# MyPulseSensor.net
KiCad netlist of a schematic drawn in EAGLE
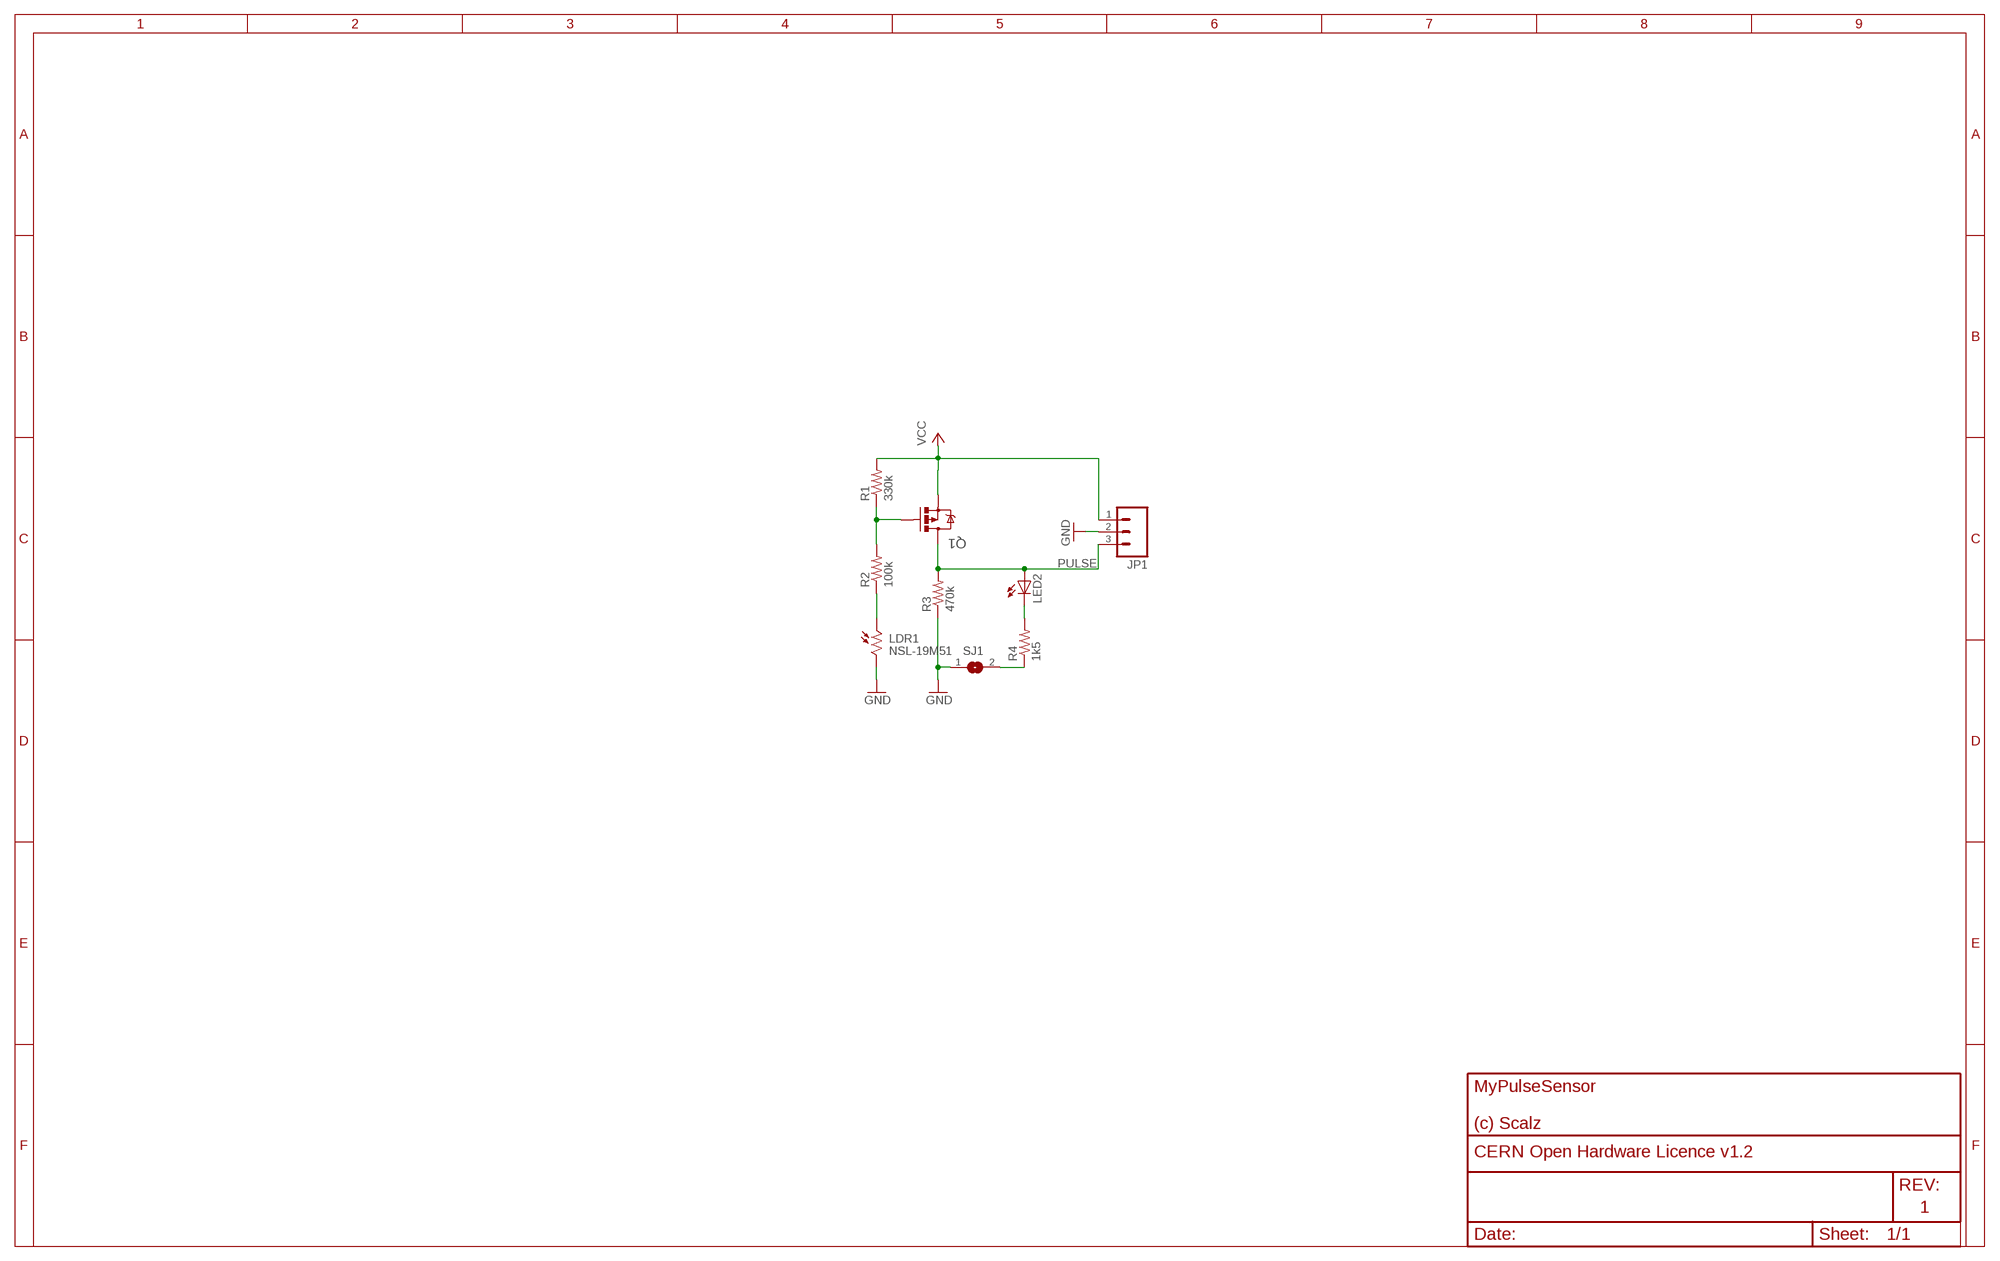
[diagram p0: schematic, sheet 1]

(export (version "E")
  (design (tool "Eeschema 10.0.6"))
  (components
    (comp (ref "JP1")
      (value "M03PTH")
      (footprint "eagle-import:1X03")
      (libsource (lib "eagle-import") (part "M03PTH"))
    )
    (comp (ref "LDR1")
      (value "NSL-19M51")
      (footprint "eagle-import:PHOTORESISTOR_TO18")
      (libsource (lib "eagle-import") (part "NSL-19M51"))
    )
    (comp (ref "LED2")
      (value "LED5MM")
      (footprint "eagle-import:LED5MM")
      (libsource (lib "eagle-import") (part "LED5MM"))
    )
    (comp (ref "Q1")
      (value "SI2399DS-T1-GE3")
      (footprint "eagle-import:SOT95P237X112-3N")
      (libsource (lib "eagle-import") (part "SI2399DS-T1-GE3"))
    )
    (comp (ref "R1")
      (value "330k")
      (footprint "eagle-import:0603-RES")
      (libsource (lib "eagle-import") (part "RESISTOR0603-RES"))
    )
    (comp (ref "R2")
      (value "100k")
      (footprint "eagle-import:0603-RES")
      (libsource (lib "eagle-import") (part "RESISTOR0603-RES"))
    )
    (comp (ref "R3")
      (value "470k")
      (footprint "eagle-import:0603-RES")
      (libsource (lib "eagle-import") (part "RESISTOR0603-RES"))
    )
    (comp (ref "R4")
      (value "1k5")
      (footprint "eagle-import:0603-RES")
      (libsource (lib "eagle-import") (part "RESISTOR0603-RES"))
    )
    (comp (ref "SJ1") (value "SJ") (footprint "eagle-import:SJ") (libsource (lib "eagle-import") (part "SJ")))
  )
  (nets
    (net (code "1") (name "/PULSE") (class "Default")
      (node (ref "JP1") (pin "3") (pinfunction "3_3") (pintype "passive"))
      (node (ref "LED2") (pin "A") (pinfunction "A_A") (pintype "passive"))
      (node (ref "Q1") (pin "3") (pinfunction "D_3") (pintype "passive"))
      (node (ref "R3") (pin "2") (pinfunction "2_2") (pintype "passive"))
    )
    (net (code "2") (name "GND") (class "Default")
      (node (ref "JP1") (pin "2") (pinfunction "2_2") (pintype "passive"))
      (node (ref "LDR1") (pin "2") (pinfunction "2_2") (pintype "passive"))
      (node (ref "R3") (pin "1") (pinfunction "1_1") (pintype "passive"))
      (node (ref "SJ1") (pin "1") (pinfunction "1_1") (pintype "passive"))
    )
    (net (code "3") (name "Net-(LDR1-Pad1)") (class "Default")
      (node (ref "LDR1") (pin "1") (pinfunction "1_1") (pintype "passive"))
      (node (ref "R2") (pin "1") (pinfunction "1_1") (pintype "passive"))
    )
    (net (code "4") (name "Net-(LED2-C)") (class "Default")
      (node (ref "LED2") (pin "K") (pinfunction "C_K") (pintype "passive"))
      (node (ref "R4") (pin "2") (pinfunction "2_2") (pintype "passive"))
    )
    (net (code "5") (name "Net-(Q1-G)") (class "Default")
      (node (ref "Q1") (pin "1") (pinfunction "G_1") (pintype "passive"))
      (node (ref "R1") (pin "1") (pinfunction "1_1") (pintype "passive"))
      (node (ref "R2") (pin "2") (pinfunction "2_2") (pintype "passive"))
    )
    (net (code "6") (name "Net-(R4-Pad1)") (class "Default")
      (node (ref "R4") (pin "1") (pinfunction "1_1") (pintype "passive"))
      (node (ref "SJ1") (pin "2") (pinfunction "2_2") (pintype "passive"))
    )
    (net (code "7") (name "VCC") (class "Default")
      (node (ref "JP1") (pin "1") (pinfunction "1_1") (pintype "passive"))
      (node (ref "Q1") (pin "2") (pinfunction "S_2") (pintype "passive"))
      (node (ref "R1") (pin "2") (pinfunction "2_2") (pintype "passive"))
    )
  )
)
